# Sheet1.net
KiCad netlist of a schematic drawn in Altium Designer
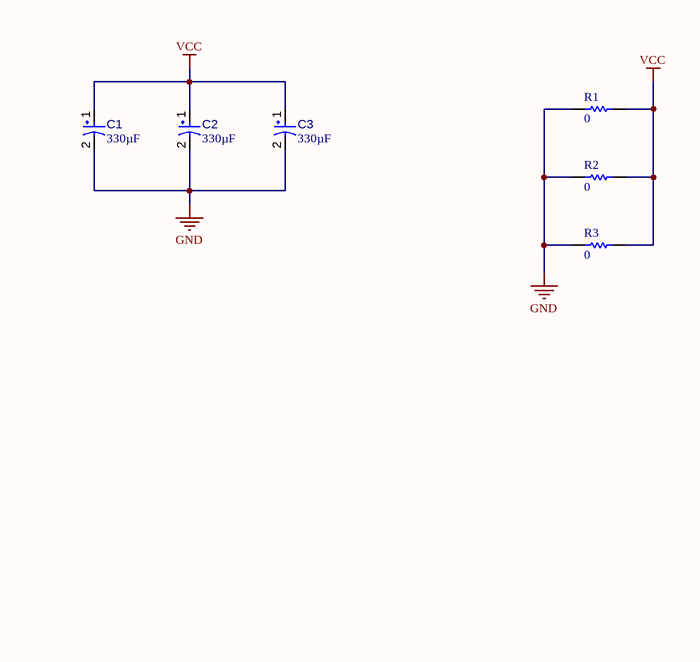
[diagram p0: Sheet1.SchDoc]

(export (version "E")
  (design (tool "Eeschema 10.0.6"))
  (components
    (comp (ref "C1")
      (value "330µF")
      (footprint "PNSC-6TPF220M5L")
      (fields (field (name "TOLERANCE") "20%") (field (name "Comment") "Capacitor 330µF +/-20% 6.3V D3"))
      (libsource (lib "LCSEmbedded") (part "CAP-P-2"))
    )
    (comp (ref "C2")
      (value "330µF")
      (footprint "PNSC-6TPF220M5L")
      (fields (field (name "TOLERANCE") "20%") (field (name "Comment") "Capacitor 330µF +/-20% 6.3V D3"))
      (libsource (lib "LCSEmbedded") (part "CAP-P-2"))
    )
    (comp (ref "C3")
      (value "330µF")
      (footprint "PNSC-6TPF220M5L")
      (fields (field (name "TOLERANCE") "20%") (field (name "Comment") "Capacitor 330µF +/-20% 6.3V D3"))
      (libsource (lib "LCSEmbedded") (part "CAP-P-2"))
    )
    (comp (ref "R1")
      (value "0")
      (footprint "RESC3216X60X45ML15T20")
      (description "Chip Resistor, 0 Ohm, +/- 5%, 0.25 W, -55 to 155 degC, 1206 (3216 Metric)")
      (fields (field (name "TOLERANCE") "5%") (field (name "POWER") "250mW"))
      (libsource (lib "LCSEmbedded") (part "RES-2"))
    )
    (comp (ref "R2")
      (value "0")
      (footprint "RESC3216X60X45ML15T20")
      (description "Chip Resistor, 0 Ohm, +/- 5%, 0.25 W, -55 to 155 degC, 1206 (3216 Metric)")
      (fields (field (name "TOLERANCE") "5%") (field (name "POWER") "250mW"))
      (libsource (lib "LCSEmbedded") (part "RES-2"))
    )
    (comp (ref "R3")
      (value "0")
      (footprint "RESC3216X60X45ML15T20")
      (description "Chip Resistor, 0 Ohm, +/- 5%, 0.25 W, -55 to 155 degC, 1206 (3216 Metric)")
      (fields (field (name "TOLERANCE") "5%") (field (name "POWER") "250mW"))
      (libsource (lib "LCSEmbedded") (part "RES-2"))
    )
  )
  (nets
    (net (code "1") (name "GND") (class "Default")
      (node (ref "C1") (pin "2") (pinfunction "2_2") (pintype "passive"))
      (node (ref "C2") (pin "2") (pinfunction "2_2") (pintype "passive"))
      (node (ref "C3") (pin "2") (pinfunction "2_2") (pintype "passive"))
      (node (ref "R1") (pin "1") (pinfunction "1_1") (pintype "passive"))
      (node (ref "R2") (pin "1") (pinfunction "1_1") (pintype "passive"))
      (node (ref "R3") (pin "1") (pinfunction "1_1") (pintype "passive"))
    )
    (net (code "2") (name "VCC") (class "Default")
      (node (ref "C1") (pin "1") (pinfunction "1_1") (pintype "passive"))
      (node (ref "C2") (pin "1") (pinfunction "1_1") (pintype "passive"))
      (node (ref "C3") (pin "1") (pinfunction "1_1") (pintype "passive"))
      (node (ref "R1") (pin "2") (pinfunction "2_2") (pintype "passive"))
      (node (ref "R2") (pin "2") (pinfunction "2_2") (pintype "passive"))
      (node (ref "R3") (pin "2") (pinfunction "2_2") (pintype "passive"))
    )
  )
)
